# Minimum_LPC2148_GPS.net
KiCad netlist of a schematic drawn in EAGLE
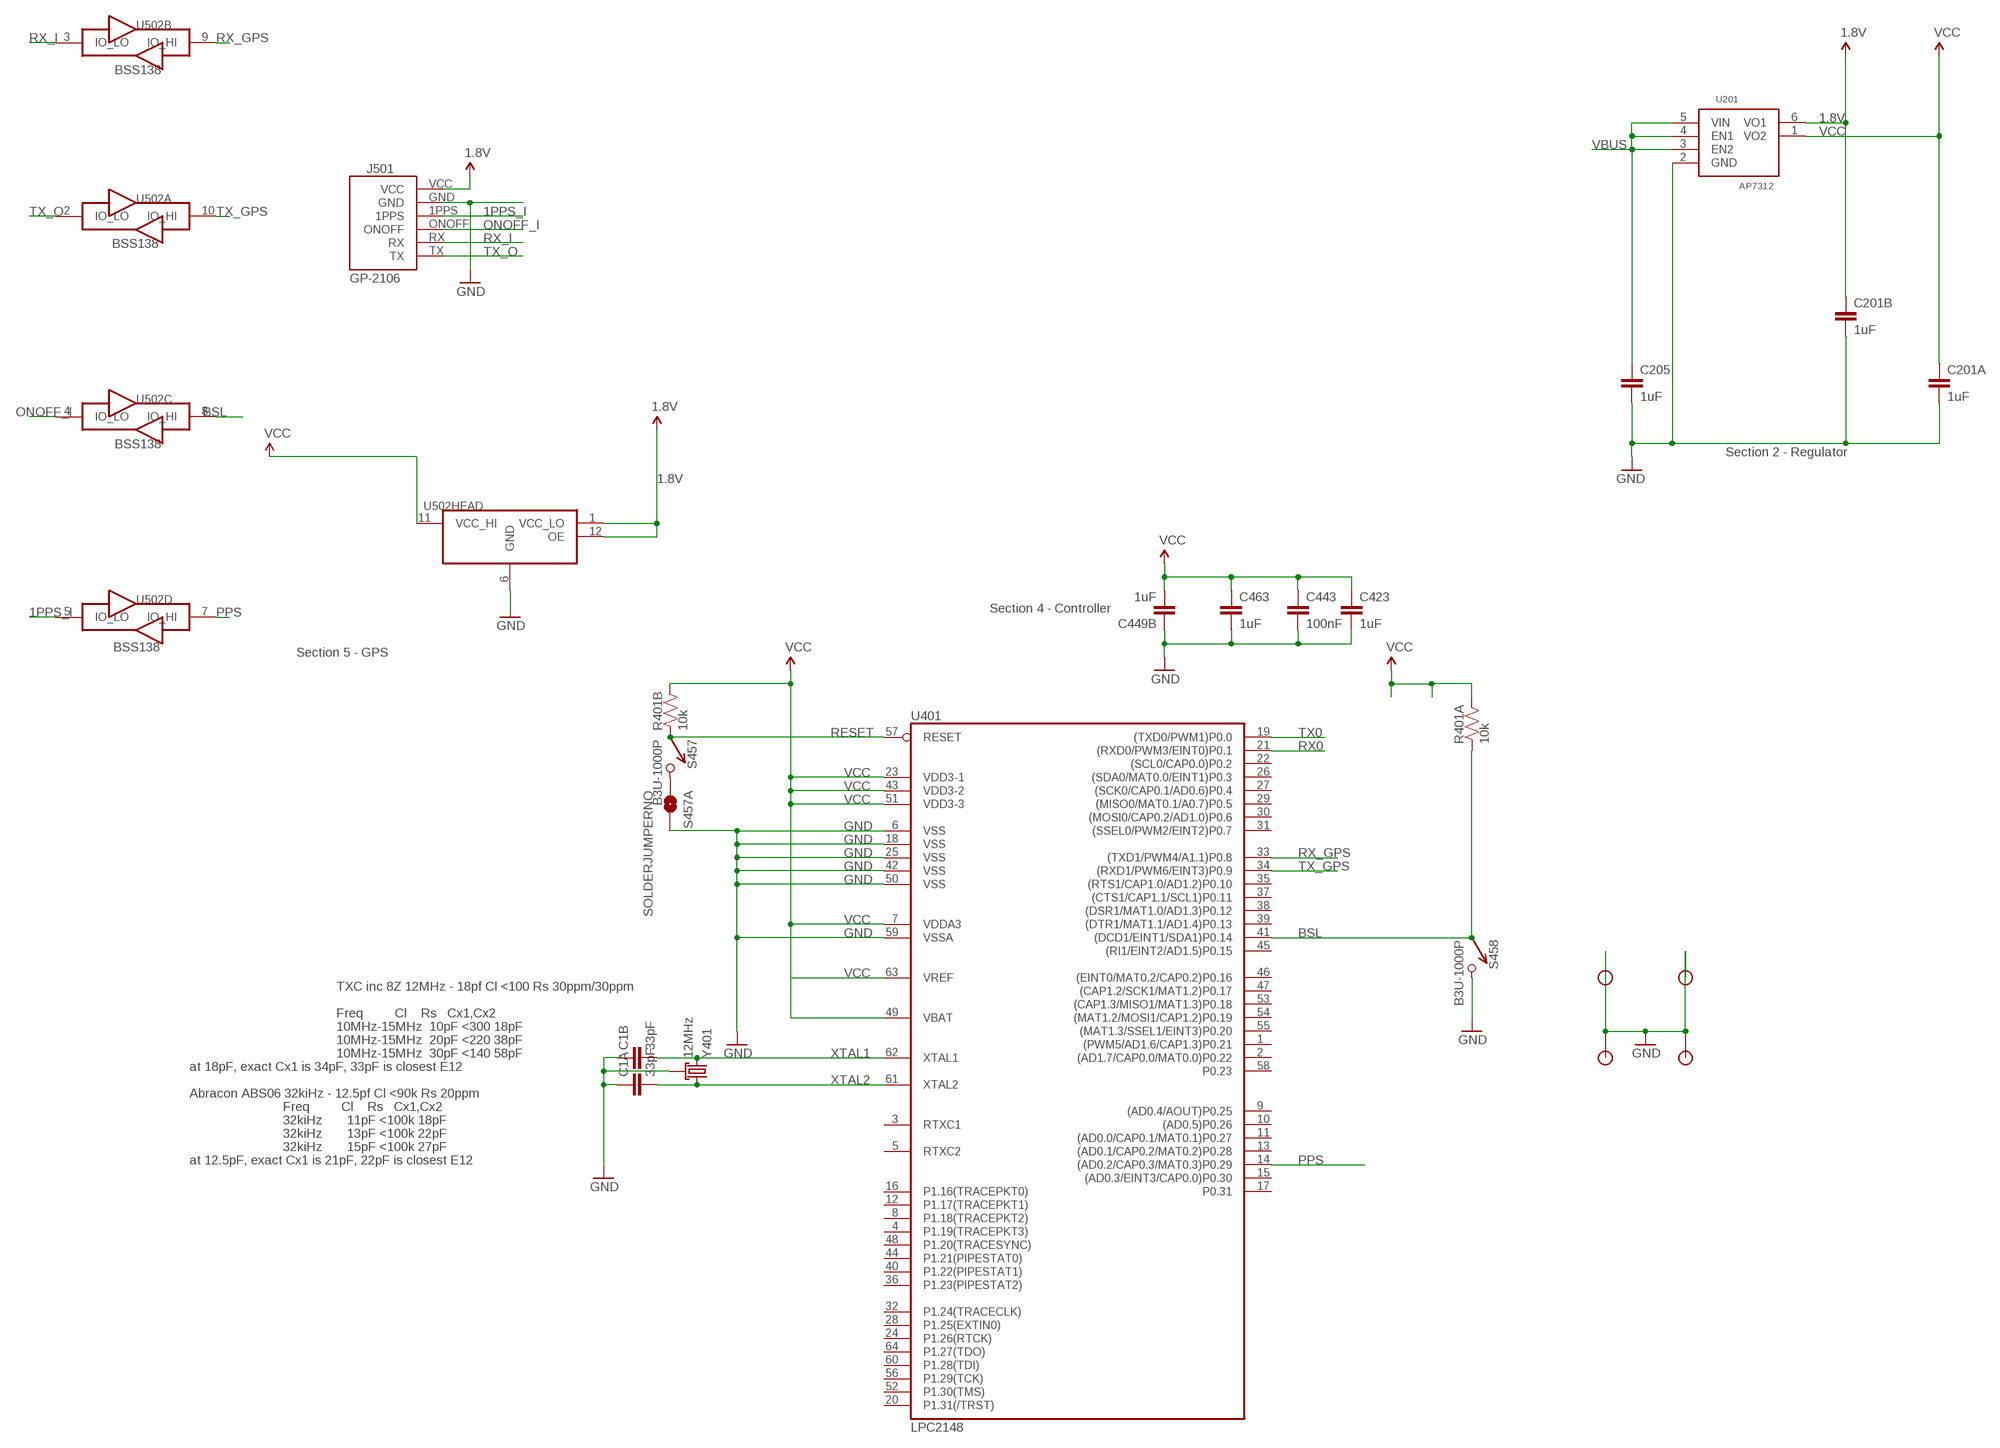
[diagram p0: schematic, sheet 1]

(export (version "E")
  (design (tool "Eeschema 10.0.6"))
  (components
    (comp (ref "C1")
      (value "33pF")
      (footprint "eagle-import:CKCM25")
      (libsource (lib "eagle-import") (part "CKCM25"))
    )
    (comp (ref "C201")
      (value "1uF")
      (footprint "eagle-import:CKCM25")
      (libsource (lib "eagle-import") (part "CKCM25"))
    )
    (comp (ref "C205")
      (value "1uF")
      (footprint "eagle-import:0402-CAP")
      (libsource (lib "eagle-import") (part "CAP0402-CAP"))
    )
    (comp (ref "C423")
      (value "1uF")
      (footprint "eagle-import:0402-CAP")
      (libsource (lib "eagle-import") (part "CAP0402-CAP"))
    )
    (comp (ref "C443")
      (value "100nF")
      (footprint "eagle-import:0402-CAP")
      (libsource (lib "eagle-import") (part "CAP0402-CAP"))
    )
    (comp (ref "C449")
      (value "1uF")
      (footprint "eagle-import:CKCM25")
      (libsource (lib "eagle-import") (part "CKCM25"))
    )
    (comp (ref "C463")
      (value "1uF")
      (footprint "eagle-import:0402-CAP")
      (libsource (lib "eagle-import") (part "CAP0402-CAP"))
    )
    (comp (ref "J501")
      (value "GP-2106")
      (footprint "eagle-import:GP-2106")
      (libsource (lib "eagle-import") (part "GP-2106"))
    )
    (comp (ref "JP1")
      (value "STANDOFF")
      (footprint "eagle-import:STANDOFF")
      (libsource (lib "eagle-import") (part "STANDOFF"))
    )
    (comp (ref "JP2")
      (value "STANDOFF")
      (footprint "eagle-import:STANDOFF")
      (libsource (lib "eagle-import") (part "STANDOFF"))
    )
    (comp (ref "JP4")
      (value "STANDOFF")
      (footprint "eagle-import:STANDOFF")
      (libsource (lib "eagle-import") (part "STANDOFF"))
    )
    (comp (ref "JP5")
      (value "STANDOFF")
      (footprint "eagle-import:STANDOFF")
      (libsource (lib "eagle-import") (part "STANDOFF"))
    )
    (comp (ref "R401")
      (value "10k")
      (footprint "eagle-import:CRA02")
      (fields (field (name "DIGIKEY") "CRA4S810KCT-ND"))
      (libsource (lib "eagle-import") (part "RP2EXB24V"))
    )
    (comp (ref "S457")
      (value "B3U-1000P")
      (footprint "eagle-import:B3U-1000P")
      (libsource (lib "eagle-import") (part "B3U-1000P"))
    )
    (comp (ref "S457A")
      (value "SOLDERJUMPERNO")
      (footprint "eagle-import:SJ_2S-NO")
      (libsource (lib "eagle-import") (part "SOLDERJUMPERNO"))
    )
    (comp (ref "S458")
      (value "B3U-1000P")
      (footprint "eagle-import:B3U-1000P")
      (libsource (lib "eagle-import") (part "B3U-1000P"))
    )
    (comp (ref "U201")
      (value "AP7312")
      (footprint "eagle-import:SOT-23-6")
      (libsource (lib "eagle-import") (part "AP73X2"))
    )
    (comp (ref "U401")
      (value "LPC2148")
      (footprint "eagle-import:SQFP-S-10X10-64")
      (libsource (lib "eagle-import") (part "LPC213X"))
    )
    (comp (ref "U502")
      (value "TXB0104RUT")
      (footprint "eagle-import:R-PUQFN-N12")
      (libsource (lib "eagle-import") (part "TXB0104RUT"))
    )
    (comp (ref "Y401")
      (value "12MHz")
      (footprint "eagle-import:CRYSTAL_SMD_2MM_2_5MM")
      (libsource (lib "eagle-import") (part "CX2520"))
    )
  )
  (nets
    (net (code "1") (name "/1PPS_I") (class "Default")
      (node (ref "J501") (pin "1PPS") (pinfunction "1PPS_1PPS") (pintype "bidirectional"))
      (node (ref "U502") (pin "5") (pinfunction "IO_LO_5") (pintype "bidirectional"))
    )
    (net (code "2") (name "/BSL") (class "Default")
      (node (ref "R401") (pin "1") (pinfunction "1_1") (pintype "passive"))
      (node (ref "S458") (pin "P$1") (pinfunction "1_P$1") (pintype "bidirectional"))
      (node (ref "U401") (pin "41") (pinfunction "(DCD1/EINT1/SDA1)P0.14_41") (pintype "bidirectional"))
      (node (ref "U502") (pin "8") (pinfunction "IO_HI_8") (pintype "bidirectional"))
    )
    (net (code "3") (name "/ONOFF_I") (class "Default")
      (node (ref "J501") (pin "ONOFF") (pinfunction "ONOFF_ONOFF") (pintype "bidirectional"))
      (node (ref "U502") (pin "4") (pinfunction "IO_LO_4") (pintype "bidirectional"))
    )
    (net (code "4") (name "/PPS") (class "Default")
      (node (ref "U401") (pin "14") (pinfunction "(AD0.2/CAP0.3/MAT0.3)P0.29_14") (pintype "bidirectional"))
      (node (ref "U502") (pin "7") (pinfunction "IO_HI_7") (pintype "bidirectional"))
    )
    (net (code "5") (name "/RESET") (class "Default")
      (node (ref "R401") (pin "2") (pinfunction "1_2") (pintype "passive"))
      (node (ref "S457") (pin "P$1") (pinfunction "1_P$1") (pintype "bidirectional"))
      (node (ref "U401") (pin "57") (pinfunction "RESET_57") (pintype "input"))
    )
    (net (code "6") (name "/RX0") (class "Default")
      (node (ref "U401") (pin "21") (pinfunction "(RXD0/PWM3/EINT0)P0.1_21") (pintype "bidirectional"))
    )
    (net (code "7") (name "/RX_GPS") (class "Default")
      (node (ref "U401") (pin "33") (pinfunction "(TXD1/PWM4/A1.1)P0.8_33") (pintype "bidirectional"))
      (node (ref "U502") (pin "9") (pinfunction "IO_HI_9") (pintype "bidirectional"))
    )
    (net (code "8") (name "/RX_I") (class "Default")
      (node (ref "J501") (pin "RX") (pinfunction "RX_RX") (pintype "bidirectional"))
      (node (ref "U502") (pin "3") (pinfunction "IO_LO_3") (pintype "bidirectional"))
    )
    (net (code "9") (name "/TX0") (class "Default")
      (node (ref "U401") (pin "19") (pinfunction "(TXD0/PWM1)P0.0_19") (pintype "bidirectional"))
    )
    (net (code "10") (name "/TX_GPS") (class "Default")
      (node (ref "U401") (pin "34") (pinfunction "(RXD1/PWM6/EINT3)P0.9_34") (pintype "bidirectional"))
      (node (ref "U502") (pin "10") (pinfunction "IO_HI_10") (pintype "bidirectional"))
    )
    (net (code "11") (name "/TX_O") (class "Default")
      (node (ref "J501") (pin "TX") (pinfunction "TX_TX") (pintype "bidirectional"))
      (node (ref "U502") (pin "2") (pinfunction "IO_LO_2") (pintype "bidirectional"))
    )
    (net (code "12") (name "/VBUS") (class "Default")
      (node (ref "C205") (pin "1") (pinfunction "1_1") (pintype "passive"))
      (node (ref "U201") (pin "3") (pinfunction "EN2_3") (pintype "bidirectional"))
      (node (ref "U201") (pin "4") (pinfunction "EN1_4") (pintype "bidirectional"))
      (node (ref "U201") (pin "5") (pinfunction "VIN_5") (pintype "bidirectional"))
    )
    (net (code "13") (name "/XTAL1") (class "Default")
      (node (ref "C1") (pin "3") (pinfunction "2_3") (pintype "passive"))
      (node (ref "U401") (pin "62") (pinfunction "XTAL1_62") (pintype "input"))
      (node (ref "Y401") (pin "3") (pinfunction "2_3") (pintype "passive"))
    )
    (net (code "14") (name "/XTAL2") (class "Default")
      (node (ref "C1") (pin "4") (pinfunction "2_4") (pintype "passive"))
      (node (ref "U401") (pin "61") (pinfunction "XTAL2_61") (pintype "output"))
      (node (ref "Y401") (pin "1") (pinfunction "1_1") (pintype "passive"))
    )
    (net (code "15") (name "1.8V") (class "Default")
      (node (ref "C201") (pin "2") (pinfunction "1_2") (pintype "passive"))
      (node (ref "J501") (pin "VCC") (pinfunction "VCC_VCC") (pintype "bidirectional"))
      (node (ref "U201") (pin "6") (pinfunction "VO1_6") (pintype "bidirectional"))
      (node (ref "U502") (pin "1") (pinfunction "VCC_LO_1") (pintype "power_in"))
      (node (ref "U502") (pin "12") (pinfunction "OE_12") (pintype "bidirectional"))
    )
    (net (code "16") (name "GND") (class "Default")
      (node (ref "C1") (pin "1") (pinfunction "1_1") (pintype "passive"))
      (node (ref "C1") (pin "2") (pinfunction "1_2") (pintype "passive"))
      (node (ref "C201") (pin "3") (pinfunction "2_3") (pintype "passive"))
      (node (ref "C201") (pin "4") (pinfunction "2_4") (pintype "passive"))
      (node (ref "C205") (pin "2") (pinfunction "2_2") (pintype "passive"))
      (node (ref "C423") (pin "2") (pinfunction "2_2") (pintype "passive"))
      (node (ref "C443") (pin "2") (pinfunction "2_2") (pintype "passive"))
      (node (ref "C449") (pin "2") (pinfunction "1_2") (pintype "passive"))
      (node (ref "C463") (pin "2") (pinfunction "2_2") (pintype "passive"))
      (node (ref "J501") (pin "GND") (pinfunction "GND_GND") (pintype "bidirectional"))
      (node (ref "JP1") (pin "P$1") (pinfunction "P$1_P$1") (pintype "bidirectional"))
      (node (ref "JP2") (pin "P$1") (pinfunction "P$1_P$1") (pintype "bidirectional"))
      (node (ref "JP4") (pin "P$1") (pinfunction "P$1_P$1") (pintype "bidirectional"))
      (node (ref "JP5") (pin "P$1") (pinfunction "P$1_P$1") (pintype "bidirectional"))
      (node (ref "S457A") (pin "2") (pinfunction "2_2") (pintype "passive"))
      (node (ref "S458") (pin "P$2") (pinfunction "2_P$2") (pintype "bidirectional"))
      (node (ref "U201") (pin "2") (pinfunction "GND_2") (pintype "bidirectional"))
      (node (ref "U401") (pin "18") (pinfunction "VSS_18") (pintype "power_in"))
      (node (ref "U401") (pin "25") (pinfunction "VSS_25") (pintype "power_in"))
      (node (ref "U401") (pin "42") (pinfunction "VSS_42") (pintype "power_in"))
      (node (ref "U401") (pin "50") (pinfunction "VSS_50") (pintype "power_in"))
      (node (ref "U401") (pin "59") (pinfunction "VSSA_59") (pintype "power_in"))
      (node (ref "U401") (pin "6") (pinfunction "VSS_6") (pintype "power_in"))
      (node (ref "U502") (pin "6") (pinfunction "GND_6") (pintype "power_in"))
      (node (ref "Y401") (pin "2") (pinfunction "GND_2") (pintype "passive"))
      (node (ref "Y401") (pin "4") (pinfunction "GND_4") (pintype "passive"))
    )
    (net (code "17") (name "Net-(S457-2)") (class "Default")
      (node (ref "S457") (pin "P$2") (pinfunction "2_P$2") (pintype "bidirectional"))
      (node (ref "S457A") (pin "1") (pinfunction "1_1") (pintype "passive"))
    )
    (net (code "18") (name "VCC") (class "Default")
      (node (ref "C201") (pin "1") (pinfunction "1_1") (pintype "passive"))
      (node (ref "C423") (pin "1") (pinfunction "1_1") (pintype "passive"))
      (node (ref "C443") (pin "1") (pinfunction "1_1") (pintype "passive"))
      (node (ref "C449") (pin "3") (pinfunction "2_3") (pintype "passive"))
      (node (ref "C463") (pin "1") (pinfunction "1_1") (pintype "passive"))
      (node (ref "R401") (pin "3") (pinfunction "2_3") (pintype "passive"))
      (node (ref "R401") (pin "4") (pinfunction "2_4") (pintype "passive"))
      (node (ref "U201") (pin "1") (pinfunction "VO2_1") (pintype "bidirectional"))
      (node (ref "U401") (pin "23") (pinfunction "VDD3-1_23") (pintype "power_in"))
      (node (ref "U401") (pin "43") (pinfunction "VDD3-2_43") (pintype "power_in"))
      (node (ref "U401") (pin "49") (pinfunction "VBAT_49") (pintype "power_in"))
      (node (ref "U401") (pin "51") (pinfunction "VDD3-3_51") (pintype "power_in"))
      (node (ref "U401") (pin "63") (pinfunction "VREF_63") (pintype "input"))
      (node (ref "U401") (pin "7") (pinfunction "VDDA3_7") (pintype "power_in"))
      (node (ref "U502") (pin "11") (pinfunction "VCC_HI_11") (pintype "power_in"))
    )
    (net (code "19") (name "unconnected-(U401-(AD0.0{slash}CAP0.1{slash}MAT0.1)P0.27-Pad11)") (class "Default")
      (node (ref "U401") (pin "11") (pinfunction "(AD0.0/CAP0.1/MAT0.1)P0.27_11") (pintype "bidirectional"))
    )
    (net (code "20") (name "unconnected-(U401-(AD0.1{slash}CAP0.2{slash}MAT0.2)P0.28-Pad13)") (class "Default")
      (node (ref "U401") (pin "13") (pinfunction "(AD0.1/CAP0.2/MAT0.2)P0.28_13") (pintype "bidirectional"))
    )
    (net (code "21") (name "unconnected-(U401-(AD0.3{slash}EINT3{slash}CAP0.0)P0.30-Pad15)") (class "Default")
      (node (ref "U401") (pin "15") (pinfunction "(AD0.3/EINT3/CAP0.0)P0.30_15") (pintype "bidirectional"))
    )
    (net (code "22") (name "unconnected-(U401-(AD0.4{slash}AOUT)P0.25-Pad9)") (class "Default")
      (node (ref "U401") (pin "9") (pinfunction "(AD0.4/AOUT)P0.25_9") (pintype "bidirectional"))
    )
    (net (code "23") (name "unconnected-(U401-(AD0.5)P0.26-Pad10)") (class "Default")
      (node (ref "U401") (pin "10") (pinfunction "(AD0.5)P0.26_10") (pintype "bidirectional"))
    )
    (net (code "24") (name "unconnected-(U401-(AD1.7{slash}CAP0.0{slash}MAT0.0)P0.22-Pad2)") (class "Default")
      (node (ref "U401") (pin "2") (pinfunction "(AD1.7/CAP0.0/MAT0.0)P0.22_2") (pintype "bidirectional"))
    )
    (net (code "25") (name "unconnected-(U401-(CAP1.2{slash}SCK1{slash}MAT1.2)P0.17-Pad47)") (class "Default")
      (node (ref "U401") (pin "47") (pinfunction "(CAP1.2/SCK1/MAT1.2)P0.17_47") (pintype "bidirectional"))
    )
    (net (code "26") (name "unconnected-(U401-(CAP1.3{slash}MISO1{slash}MAT1.3)P0.18-Pad53)") (class "Default")
      (node (ref "U401") (pin "53") (pinfunction "(CAP1.3/MISO1/MAT1.3)P0.18_53") (pintype "bidirectional"))
    )
    (net (code "27") (name "unconnected-(U401-(CTS1{slash}CAP1.1{slash}SCL1)P0.11-Pad37)") (class "Default")
      (node (ref "U401") (pin "37") (pinfunction "(CTS1/CAP1.1/SCL1)P0.11_37") (pintype "bidirectional"))
    )
    (net (code "28") (name "unconnected-(U401-(DSR1{slash}MAT1.0{slash}AD1.3)P0.12-Pad38)") (class "Default")
      (node (ref "U401") (pin "38") (pinfunction "(DSR1/MAT1.0/AD1.3)P0.12_38") (pintype "bidirectional"))
    )
    (net (code "29") (name "unconnected-(U401-(DTR1{slash}MAT1.1{slash}AD1.4)P0.13-Pad39)") (class "Default")
      (node (ref "U401") (pin "39") (pinfunction "(DTR1/MAT1.1/AD1.4)P0.13_39") (pintype "bidirectional"))
    )
    (net (code "30") (name "unconnected-(U401-(EINT0{slash}MAT0.2{slash}CAP0.2)P0.16-Pad46)") (class "Default")
      (node (ref "U401") (pin "46") (pinfunction "(EINT0/MAT0.2/CAP0.2)P0.16_46") (pintype "bidirectional"))
    )
    (net (code "31") (name "unconnected-(U401-(MAT1.2{slash}MOSI1{slash}CAP1.2)P0.19-Pad54)") (class "Default")
      (node (ref "U401") (pin "54") (pinfunction "(MAT1.2/MOSI1/CAP1.2)P0.19_54") (pintype "bidirectional"))
    )
    (net (code "32") (name "unconnected-(U401-(MAT1.3{slash}SSEL1{slash}EINT3)P0.20-Pad55)") (class "Default")
      (node (ref "U401") (pin "55") (pinfunction "(MAT1.3/SSEL1/EINT3)P0.20_55") (pintype "bidirectional"))
    )
    (net (code "33") (name "unconnected-(U401-(MISO0{slash}MAT0.1{slash}A0.7)P0.5-Pad29)") (class "Default")
      (node (ref "U401") (pin "29") (pinfunction "(MISO0/MAT0.1/A0.7)P0.5_29") (pintype "bidirectional"))
    )
    (net (code "34") (name "unconnected-(U401-(MOSI0{slash}CAP0.2{slash}AD1.0)P0.6-Pad30)") (class "Default")
      (node (ref "U401") (pin "30") (pinfunction "(MOSI0/CAP0.2/AD1.0)P0.6_30") (pintype "bidirectional"))
    )
    (net (code "35") (name "unconnected-(U401-(PWM5{slash}AD1.6{slash}CAP1.3)P0.21-Pad1)") (class "Default")
      (node (ref "U401") (pin "1") (pinfunction "(PWM5/AD1.6/CAP1.3)P0.21_1") (pintype "bidirectional"))
    )
    (net (code "36") (name "unconnected-(U401-(RI1{slash}EINT2{slash}AD1.5)P0.15-Pad45)") (class "Default")
      (node (ref "U401") (pin "45") (pinfunction "(RI1/EINT2/AD1.5)P0.15_45") (pintype "bidirectional"))
    )
    (net (code "37") (name "unconnected-(U401-(RTS1{slash}CAP1.0{slash}AD1.2)P0.10-Pad35)") (class "Default")
      (node (ref "U401") (pin "35") (pinfunction "(RTS1/CAP1.0/AD1.2)P0.10_35") (pintype "bidirectional"))
    )
    (net (code "38") (name "unconnected-(U401-(SCK0{slash}CAP0.1{slash}AD0.6)P0.4-Pad27)") (class "Default")
      (node (ref "U401") (pin "27") (pinfunction "(SCK0/CAP0.1/AD0.6)P0.4_27") (pintype "bidirectional"))
    )
    (net (code "39") (name "unconnected-(U401-(SCL0{slash}CAP0.0)P0.2-Pad22)") (class "Default")
      (node (ref "U401") (pin "22") (pinfunction "(SCL0/CAP0.0)P0.2_22") (pintype "bidirectional"))
    )
    (net (code "40") (name "unconnected-(U401-(SDA0{slash}MAT0.0{slash}EINT1)P0.3-Pad26)") (class "Default")
      (node (ref "U401") (pin "26") (pinfunction "(SDA0/MAT0.0/EINT1)P0.3_26") (pintype "bidirectional"))
    )
    (net (code "41") (name "unconnected-(U401-(SSEL0{slash}PWM2{slash}EINT2)P0.7-Pad31)") (class "Default")
      (node (ref "U401") (pin "31") (pinfunction "(SSEL0/PWM2/EINT2)P0.7_31") (pintype "bidirectional"))
    )
    (net (code "42") (name "unconnected-(U401-P0.23-Pad58)") (class "Default")
      (node (ref "U401") (pin "58") (pinfunction "P0.23_58") (pintype "bidirectional"))
    )
    (net (code "43") (name "unconnected-(U401-P0.31-Pad17)") (class "Default")
      (node (ref "U401") (pin "17") (pinfunction "P0.31_17") (pintype "output"))
    )
    (net (code "44") (name "unconnected-(U401-P1.16(TRACEPKT0)-Pad16)") (class "Default")
      (node (ref "U401") (pin "16") (pinfunction "P1.16(TRACEPKT0)_16") (pintype "bidirectional"))
    )
    (net (code "45") (name "unconnected-(U401-P1.17(TRACEPKT1)-Pad12)") (class "Default")
      (node (ref "U401") (pin "12") (pinfunction "P1.17(TRACEPKT1)_12") (pintype "bidirectional"))
    )
    (net (code "46") (name "unconnected-(U401-P1.18(TRACEPKT2)-Pad8)") (class "Default")
      (node (ref "U401") (pin "8") (pinfunction "P1.18(TRACEPKT2)_8") (pintype "bidirectional"))
    )
    (net (code "47") (name "unconnected-(U401-P1.19(TRACEPKT3)-Pad4)") (class "Default")
      (node (ref "U401") (pin "4") (pinfunction "P1.19(TRACEPKT3)_4") (pintype "bidirectional"))
    )
    (net (code "48") (name "unconnected-(U401-P1.20(TRACESYNC)-Pad48)") (class "Default")
      (node (ref "U401") (pin "48") (pinfunction "P1.20(TRACESYNC)_48") (pintype "bidirectional"))
    )
    (net (code "49") (name "unconnected-(U401-P1.21(PIPESTAT0)-Pad44)") (class "Default")
      (node (ref "U401") (pin "44") (pinfunction "P1.21(PIPESTAT0)_44") (pintype "bidirectional"))
    )
    (net (code "50") (name "unconnected-(U401-P1.22(PIPESTAT1)-Pad40)") (class "Default")
      (node (ref "U401") (pin "40") (pinfunction "P1.22(PIPESTAT1)_40") (pintype "bidirectional"))
    )
    (net (code "51") (name "unconnected-(U401-P1.23(PIPESTAT2)-Pad36)") (class "Default")
      (node (ref "U401") (pin "36") (pinfunction "P1.23(PIPESTAT2)_36") (pintype "bidirectional"))
    )
    (net (code "52") (name "unconnected-(U401-P1.24(TRACECLK)-Pad32)") (class "Default")
      (node (ref "U401") (pin "32") (pinfunction "P1.24(TRACECLK)_32") (pintype "bidirectional"))
    )
    (net (code "53") (name "unconnected-(U401-P1.25(EXTIN0)-Pad28)") (class "Default")
      (node (ref "U401") (pin "28") (pinfunction "P1.25(EXTIN0)_28") (pintype "bidirectional"))
    )
    (net (code "54") (name "unconnected-(U401-P1.26(RTCK)-Pad24)") (class "Default")
      (node (ref "U401") (pin "24") (pinfunction "P1.26(RTCK)_24") (pintype "bidirectional"))
    )
    (net (code "55") (name "unconnected-(U401-P1.27(TDO)-Pad64)") (class "Default")
      (node (ref "U401") (pin "64") (pinfunction "P1.27(TDO)_64") (pintype "bidirectional"))
    )
    (net (code "56") (name "unconnected-(U401-P1.28(TDI)-Pad60)") (class "Default")
      (node (ref "U401") (pin "60") (pinfunction "P1.28(TDI)_60") (pintype "bidirectional"))
    )
    (net (code "57") (name "unconnected-(U401-P1.29(TCK)-Pad56)") (class "Default")
      (node (ref "U401") (pin "56") (pinfunction "P1.29(TCK)_56") (pintype "bidirectional"))
    )
    (net (code "58") (name "unconnected-(U401-P1.30(TMS)-Pad52)") (class "Default")
      (node (ref "U401") (pin "52") (pinfunction "P1.30(TMS)_52") (pintype "bidirectional"))
    )
    (net (code "59") (name "unconnected-(U401-P1.31({slash}TRST)-Pad20)") (class "Default")
      (node (ref "U401") (pin "20") (pinfunction "P1.31(/TRST)_20") (pintype "bidirectional"))
    )
    (net (code "60") (name "unconnected-(U401-RTXC1-Pad3)") (class "Default")
      (node (ref "U401") (pin "3") (pinfunction "RTXC1_3") (pintype "input"))
    )
    (net (code "61") (name "unconnected-(U401-RTXC2-Pad5)") (class "Default")
      (node (ref "U401") (pin "5") (pinfunction "RTXC2_5") (pintype "output"))
    )
  )
)
